# easyeda.net
KiCad netlist of a schematic drawn in EasyEDA
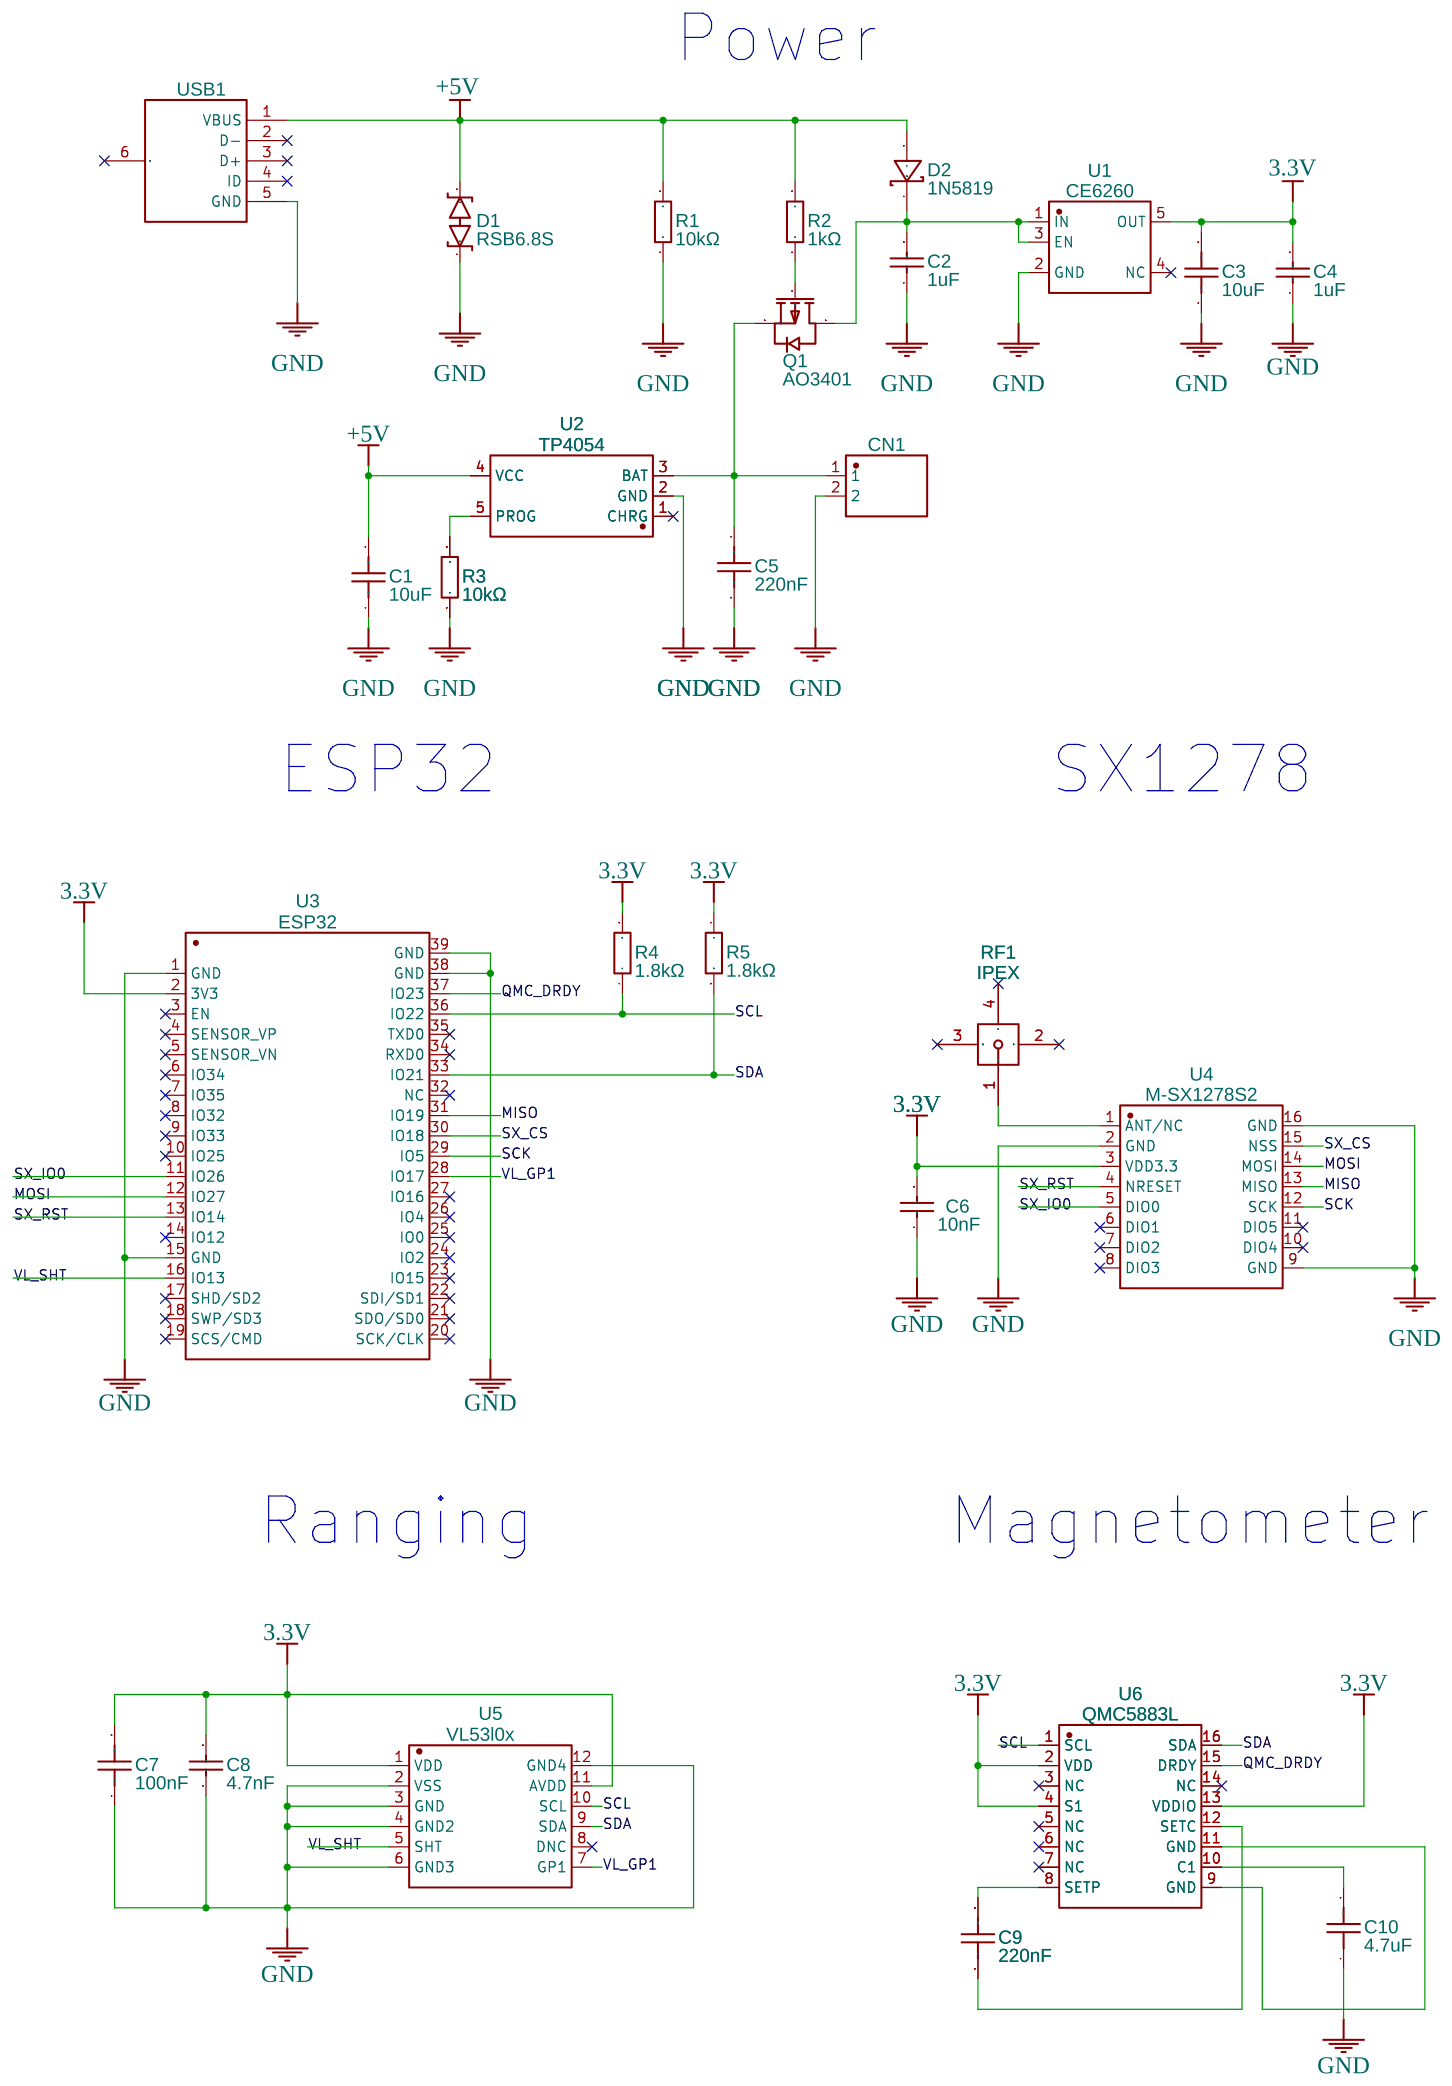
[diagram p0: schematic sheet]

(export (version "E")
  (design (tool "Eeschema 10.0.6"))
  (components
    (comp (ref "C1")
      (value "10uF")
      (fields
        (field (name "Manufacturer Part") "CL10A106KP8NNNC")
        (field (name "Manufacturer") "SAMSUNG(三星)")
      )
      (libsource (lib "") (part "CL10A106KP8NNNC"))
    )
    (comp (ref "C2")
      (value "1uF")
      (fields
        (field (name "Manufacturer Part") "CL05A105KP5NNNC")
        (field (name "Manufacturer") "SAMSUNG(三星)")
      )
      (libsource (lib "") (part "CL05A105KP5NNNC"))
    )
    (comp (ref "C3")
      (value "10uF")
      (fields
        (field (name "Manufacturer Part") "CL10A106KP8NNNC")
        (field (name "Manufacturer") "SAMSUNG(三星)")
      )
      (libsource (lib "") (part "CL10A106KP8NNNC"))
    )
    (comp (ref "C4")
      (value "1uF")
      (fields
        (field (name "Manufacturer Part") "CL05A105KP5NNNC")
        (field (name "Manufacturer") "SAMSUNG(三星)")
      )
      (libsource (lib "") (part "CL05A105KP5NNNC"))
    )
    (comp (ref "C5")
      (value "220nF")
      (fields
        (field (name "Manufacturer Part") "CL05A224KP5NNNC")
        (field (name "Manufacturer") "SAMSUNG(三星)")
      )
      (libsource (lib "") (part "CL05A224KP5NNNC"))
    )
    (comp (ref "C6")
      (value "10nF")
      (fields
        (field (name "Manufacturer Part") "CL10B103KB8NNNC")
        (field (name "Manufacturer") "SAMSUNG(三星)")
      )
      (libsource (lib "") (part "CL10B103KB8NNNC"))
    )
    (comp (ref "C7")
      (value "100nF")
      (fields
        (field (name "Manufacturer Part") "CL10B104KB8NNNC")
        (field (name "Manufacturer") "SAMSUNG(三星)")
      )
      (libsource (lib "") (part "CL10B104KB8NNNC"))
    )
    (comp (ref "C8")
      (value "4.7nF")
      (fields
        (field (name "Manufacturer Part") "CL10B472KB8NNNC")
        (field (name "Manufacturer") "SAMSUNG(三星)")
      )
      (libsource (lib "") (part "CL10B472KB8NNNC"))
    )
    (comp (ref "C9")
      (value "220nF")
      (fields (field (name "Manufacturer Part") "CGA2B1X7R1A224K050BC") (field (name "Manufacturer") "TDK"))
      (libsource (lib "") (part "CGA2B1X7R1A224K050BC"))
    )
    (comp (ref "C10")
      (value "4.7uF")
      (fields
        (field (name "Manufacturer Part") "CL05A475MQ5NRNC")
        (field (name "Manufacturer") "SAMSUNG(三星)")
      )
      (libsource (lib "") (part "CL05A475MQ5NRNC_C307423"))
    )
    (comp (ref "CN1")
      (value "B2B-XH-A (LF)(SN)")
      (fields (field (name "Manufacturer Part") "B2B-XH-A(LF)(SN)") (field (name "Manufacturer") "JST"))
      (libsource (lib "") (part "B2B-XH-A (LF)(SN)"))
    )
    (comp (ref "D1") (value "RSB6.8S") (libsource (lib "") (part "RSB6.8S")))
    (comp (ref "D2")
      (value "1N5819")
      (fields (field (name "Manufacturer") "KEXIN(科信)"))
      (libsource (lib "") (part "1N5819_C437199"))
    )
    (comp (ref "Q1")
      (value "AO3401")
      (fields (field (name "Manufacturer") "YONGYUTAI(永裕泰)"))
      (libsource (lib "") (part "AO3401_C2891730"))
    )
    (comp (ref "R1")
      (value "10kΩ")
      (fields
        (field (name "Manufacturer Part") "0402WGF1002TCE")
        (field (name "Manufacturer") "UNI-ROYAL(厚声)")
      )
      (libsource (lib "") (part "0402WGF1002TCE"))
    )
    (comp (ref "R2")
      (value "1kΩ")
      (fields
        (field (name "Manufacturer Part") "0402WGF1001TCE")
        (field (name "Manufacturer") "UNI-ROYAL(厚声)")
      )
      (libsource (lib "") (part "0402WGF1001TCE"))
    )
    (comp (ref "R3")
      (value "10kΩ")
      (fields
        (field (name "Manufacturer Part") "0402WGF1002TCE")
        (field (name "Manufacturer") "UNI-ROYAL(厚声)")
      )
      (libsource (lib "") (part "0402WGF1002TCE"))
    )
    (comp (ref "R4")
      (value "1.8kΩ")
      (fields
        (field (name "Manufacturer Part") "0402WGF1801TCE")
        (field (name "Manufacturer") "UNI-ROYAL(厚声)")
      )
      (libsource (lib "") (part "0402WGF1801TCE"))
    )
    (comp (ref "R5")
      (value "1.8kΩ")
      (fields
        (field (name "Manufacturer Part") "0402WGF1801TCE")
        (field (name "Manufacturer") "UNI-ROYAL(厚声)")
      )
      (libsource (lib "") (part "0402WGF1801TCE_1"))
    )
    (comp (ref "RF1")
      (value "IPEX")
      (fields (field (name "Manufacturer Part") "IPEX-4") (field (name "Manufacturer") "Ziisor(致哲)"))
      (libsource (lib "") (part "IPEX-4"))
    )
    (comp (ref "U1") (value "CE6260") (libsource (lib "") (part "CE6260_LDO Regulator")))
    (comp (ref "U2")
      (value "TP4054")
      (fields
        (field (name "Manufacturer Part") "TP4054-42-SOT25R")
        (field (name "Manufacturer") "TOPPOWER(南京拓微)")
      )
      (libsource (lib "") (part "TP4054"))
    )
    (comp (ref "U3")
      (value "ESP32")
      (fields
        (field (name "Manufacturer Part") "ESP32-WROOM-32-N4")
        (field (name "Manufacturer") "ESPRESSIF(乐鑫)")
      )
      (libsource (lib "") (part "ESP32-WROOM-32"))
    )
    (comp (ref "U4")
      (value "M-SX1278S2")
      (fields (field (name "Manufacturer") "DreamLNK(骏晔科技)"))
      (libsource (lib "") (part "M-SX1278S2"))
    )
    (comp (ref "U5")
      (value "VL53l0x")
      (fields (field (name "Manufacturer Part") "VL53L0CXV0DH/1") (field (name "Manufacturer") "ST(意法半导体)"))
      (libsource (lib "") (part "VL53L0CXV0DH/1"))
    )
    (comp (ref "U6")
      (value "QMC5883L")
      (fields (field (name "Manufacturer") "QST(上海矽睿)"))
      (libsource (lib "") (part "QMC5883L"))
    )
    (comp (ref "USB1")
      (value "U254-051T-4BH83-S1S")
      (fields (field (name "Manufacturer") "XKB Connectivity(中国星坤)"))
      (libsource (lib "") (part "U254-051T-4BH83-S1S"))
    )
  )
  (nets
    (net (code "1") (name "+5V") (class "Default")
      (node (ref "C1") (pin "2") (pinfunction "2_2") (pintype "unspecified"))
      (node (ref "D1") (pin "2") (pinfunction "2_2") (pintype "unspecified"))
      (node (ref "D2") (pin "2") (pinfunction "A_2") (pintype "unspecified"))
      (node (ref "R1") (pin "2") (pinfunction "2_2") (pintype "input"))
      (node (ref "R2") (pin "2") (pinfunction "2_2") (pintype "input"))
      (node (ref "U2") (pin "4") (pinfunction "VCC_4") (pintype "unspecified"))
      (node (ref "USB1") (pin "1") (pinfunction "VBUS_1") (pintype "input"))
    )
    (net (code "2") (name "/MISO") (class "Default")
      (node (ref "U3") (pin "31") (pinfunction "IO19_31") (pintype "unspecified"))
      (node (ref "U4") (pin "13") (pinfunction "MISO_13") (pintype "unspecified"))
    )
    (net (code "3") (name "/MOSI") (class "Default")
      (node (ref "U3") (pin "12") (pinfunction "IO27_12") (pintype "unspecified"))
      (node (ref "U4") (pin "14") (pinfunction "MOSI_14") (pintype "unspecified"))
    )
    (net (code "4") (name "/QMC_DRDY") (class "Default")
      (node (ref "U3") (pin "37") (pinfunction "IO23_37") (pintype "unspecified"))
      (node (ref "U6") (pin "15") (pinfunction "DRDY_15") (pintype "unspecified"))
    )
    (net (code "5") (name "/SCK") (class "Default")
      (node (ref "U3") (pin "29") (pinfunction "IO5_29") (pintype "unspecified"))
      (node (ref "U4") (pin "12") (pinfunction "SCK_12") (pintype "unspecified"))
    )
    (net (code "6") (name "/SCL") (class "Default")
      (node (ref "R4") (pin "1") (pinfunction "1_1") (pintype "input"))
      (node (ref "U3") (pin "36") (pinfunction "IO22_36") (pintype "unspecified"))
      (node (ref "U5") (pin "10") (pinfunction "SCL_10") (pintype "unspecified"))
      (node (ref "U6") (pin "1") (pinfunction "SCL_1") (pintype "unspecified"))
    )
    (net (code "7") (name "/SDA") (class "Default")
      (node (ref "R5") (pin "2") (pinfunction "2_2") (pintype "input"))
      (node (ref "U3") (pin "33") (pinfunction "IO21_33") (pintype "unspecified"))
      (node (ref "U5") (pin "9") (pinfunction "SDA_9") (pintype "unspecified"))
      (node (ref "U6") (pin "16") (pinfunction "SDA_16") (pintype "unspecified"))
    )
    (net (code "8") (name "/SX_CS") (class "Default")
      (node (ref "U3") (pin "30") (pinfunction "IO18_30") (pintype "unspecified"))
      (node (ref "U4") (pin "15") (pinfunction "NSS_15") (pintype "unspecified"))
    )
    (net (code "9") (name "/SX_IO0") (class "Default")
      (node (ref "U3") (pin "11") (pinfunction "IO26_11") (pintype "unspecified"))
      (node (ref "U4") (pin "5") (pinfunction "DIO0_5") (pintype "unspecified"))
    )
    (net (code "10") (name "/SX_RST") (class "Default")
      (node (ref "U3") (pin "13") (pinfunction "IO14_13") (pintype "unspecified"))
      (node (ref "U4") (pin "4") (pinfunction "NRESET_4") (pintype "unspecified"))
    )
    (net (code "11") (name "/VL_GP1") (class "Default")
      (node (ref "U3") (pin "28") (pinfunction "IO17_28") (pintype "unspecified"))
      (node (ref "U5") (pin "7") (pinfunction "GP1_7") (pintype "unspecified"))
    )
    (net (code "12") (name "/VL_SHT") (class "Default")
      (node (ref "U3") (pin "16") (pinfunction "IO13_16") (pintype "unspecified"))
      (node (ref "U5") (pin "5") (pinfunction "SHT_5") (pintype "unspecified"))
    )
    (net (code "13") (name "3.3V") (class "Default")
      (node (ref "C3") (pin "2") (pinfunction "2_2") (pintype "unspecified"))
      (node (ref "C4") (pin "2") (pinfunction "2_2") (pintype "input"))
      (node (ref "C6") (pin "2") (pinfunction "2_2") (pintype "input"))
      (node (ref "C7") (pin "2") (pinfunction "2_2") (pintype "unspecified"))
      (node (ref "C8") (pin "2") (pinfunction "2_2") (pintype "input"))
      (node (ref "R4") (pin "2") (pinfunction "2_2") (pintype "input"))
      (node (ref "R5") (pin "1") (pinfunction "1_1") (pintype "input"))
      (node (ref "U1") (pin "5") (pinfunction "OUT_5") (pintype "unspecified"))
      (node (ref "U3") (pin "2") (pinfunction "3V3_2") (pintype "unspecified"))
      (node (ref "U4") (pin "3") (pinfunction "VDD3.3_3") (pintype "unspecified"))
      (node (ref "U5") (pin "1") (pinfunction "VDD_1") (pintype "unspecified"))
      (node (ref "U5") (pin "11") (pinfunction "AVDD_11") (pintype "unspecified"))
      (node (ref "U6") (pin "13") (pinfunction "VDDIO_13") (pintype "unspecified"))
      (node (ref "U6") (pin "2") (pinfunction "VDD_2") (pintype "unspecified"))
      (node (ref "U6") (pin "4") (pinfunction "S1_4") (pintype "unspecified"))
    )
    (net (code "14") (name "GND") (class "Default")
      (node (ref "C1") (pin "1") (pinfunction "1_1") (pintype "unspecified"))
      (node (ref "C10") (pin "1") (pinfunction "1_1") (pintype "unspecified"))
      (node (ref "C2") (pin "1") (pinfunction "1_1") (pintype "input"))
      (node (ref "C3") (pin "1") (pinfunction "1_1") (pintype "unspecified"))
      (node (ref "C4") (pin "1") (pinfunction "1_1") (pintype "input"))
      (node (ref "C5") (pin "2") (pinfunction "2_2") (pintype "unspecified"))
      (node (ref "C6") (pin "1") (pinfunction "1_1") (pintype "input"))
      (node (ref "C7") (pin "1") (pinfunction "1_1") (pintype "unspecified"))
      (node (ref "C8") (pin "1") (pinfunction "1_1") (pintype "input"))
      (node (ref "CN1") (pin "2") (pinfunction "2_2") (pintype "unspecified"))
      (node (ref "D1") (pin "1") (pinfunction "1_1") (pintype "unspecified"))
      (node (ref "R1") (pin "1") (pinfunction "1_1") (pintype "input"))
      (node (ref "R3") (pin "1") (pinfunction "1_1") (pintype "input"))
      (node (ref "U1") (pin "2") (pinfunction "GND_2") (pintype "unspecified"))
      (node (ref "U2") (pin "2") (pinfunction "GND_2") (pintype "unspecified"))
      (node (ref "U3") (pin "1") (pinfunction "GND_1") (pintype "unspecified"))
      (node (ref "U3") (pin "15") (pinfunction "GND_15") (pintype "unspecified"))
      (node (ref "U3") (pin "38") (pinfunction "GND_38") (pintype "unspecified"))
      (node (ref "U3") (pin "39") (pinfunction "GND_39") (pintype "unspecified"))
      (node (ref "U4") (pin "16") (pinfunction "GND_16") (pintype "unspecified"))
      (node (ref "U4") (pin "2") (pinfunction "GND_2") (pintype "unspecified"))
      (node (ref "U4") (pin "9") (pinfunction "GND_9") (pintype "unspecified"))
      (node (ref "U5") (pin "12") (pinfunction "GND4_12") (pintype "unspecified"))
      (node (ref "U5") (pin "2") (pinfunction "VSS_2") (pintype "unspecified"))
      (node (ref "U5") (pin "3") (pinfunction "GND_3") (pintype "unspecified"))
      (node (ref "U5") (pin "4") (pinfunction "GND2_4") (pintype "unspecified"))
      (node (ref "U5") (pin "6") (pinfunction "GND3_6") (pintype "unspecified"))
      (node (ref "USB1") (pin "5") (pinfunction "GND_5") (pintype "input"))
    )
    (net (code "15") (name "Net-(D2-C)") (class "Default")
      (node (ref "C2") (pin "2") (pinfunction "2_2") (pintype "input"))
      (node (ref "D2") (pin "1") (pinfunction "C_1") (pintype "unspecified"))
      (node (ref "Q1") (pin "3") (pinfunction "D_3") (pintype "unspecified"))
      (node (ref "U1") (pin "1") (pinfunction "IN_1") (pintype "unspecified"))
      (node (ref "U1") (pin "3") (pinfunction "EN_3") (pintype "unspecified"))
    )
    (net (code "16") (name "Net-(Q1-G)") (class "Default")
      (node (ref "Q1") (pin "1") (pinfunction "G_1") (pintype "unspecified"))
      (node (ref "R2") (pin "1") (pinfunction "1_1") (pintype "input"))
    )
    (net (code "17") (name "Net-(Q1-S)") (class "Default")
      (node (ref "C5") (pin "1") (pinfunction "1_1") (pintype "unspecified"))
      (node (ref "CN1") (pin "1") (pinfunction "1_1") (pintype "unspecified"))
      (node (ref "Q1") (pin "2") (pinfunction "S_2") (pintype "unspecified"))
      (node (ref "U2") (pin "3") (pinfunction "BAT_3") (pintype "unspecified"))
    )
    (net (code "18") (name "Net-(U2-PROG)") (class "Default")
      (node (ref "R3") (pin "2") (pinfunction "2_2") (pintype "input"))
      (node (ref "U2") (pin "5") (pinfunction "PROG_5") (pintype "unspecified"))
    )
    (net (code "19") (name "Net-(U4-ANT{slash}NC)") (class "Default")
      (node (ref "RF1") (pin "1") (pinfunction "1_1") (pintype "unspecified"))
      (node (ref "U4") (pin "1") (pinfunction "ANT/NC_1") (pintype "unspecified"))
    )
    (net (code "20") (name "Net-(U6-C1)") (class "Default")
      (node (ref "C10") (pin "2") (pinfunction "2_2") (pintype "unspecified"))
      (node (ref "U6") (pin "10") (pinfunction "C1_10") (pintype "unspecified"))
    )
    (net (code "21") (name "Net-(U6-GND-Pad11)") (class "Default")
      (node (ref "U6") (pin "11") (pinfunction "GND_11") (pintype "unspecified"))
      (node (ref "U6") (pin "9") (pinfunction "GND_9") (pintype "unspecified"))
    )
    (net (code "22") (name "Net-(U6-SETC)") (class "Default")
      (node (ref "C9") (pin "1") (pinfunction "1_1") (pintype "unspecified"))
      (node (ref "U6") (pin "12") (pinfunction "SETC_12") (pintype "unspecified"))
    )
    (net (code "23") (name "Net-(U6-SETP)") (class "Default")
      (node (ref "C9") (pin "2") (pinfunction "2_2") (pintype "unspecified"))
      (node (ref "U6") (pin "8") (pinfunction "SETP_8") (pintype "unspecified"))
    )
    (net (code "24") (name "unconnected-(RF1-Pad2)") (class "Default")
      (node (ref "RF1") (pin "2") (pinfunction "2_2") (pintype "unspecified+no_connect"))
    )
    (net (code "25") (name "unconnected-(RF1-Pad3)") (class "Default")
      (node (ref "RF1") (pin "3") (pinfunction "3_3") (pintype "unspecified+no_connect"))
    )
    (net (code "26") (name "unconnected-(RF1-Pad4)") (class "Default")
      (node (ref "RF1") (pin "4") (pinfunction "4_4") (pintype "unspecified+no_connect"))
    )
    (net (code "27") (name "unconnected-(U1-NC-Pad4)") (class "Default")
      (node (ref "U1") (pin "4") (pinfunction "NC_4") (pintype "unspecified+no_connect"))
    )
    (net (code "28") (name "unconnected-(U2-CHRG-Pad1)") (class "Default")
      (node (ref "U2") (pin "1") (pinfunction "CHRG_1") (pintype "unspecified+no_connect"))
    )
    (net (code "29") (name "unconnected-(U3-EN-Pad3)") (class "Default")
      (node (ref "U3") (pin "3") (pinfunction "EN_3") (pintype "unspecified+no_connect"))
    )
    (net (code "30") (name "unconnected-(U3-IO0-Pad25)") (class "Default")
      (node (ref "U3") (pin "25") (pinfunction "IO0_25") (pintype "unspecified+no_connect"))
    )
    (net (code "31") (name "unconnected-(U3-IO2-Pad24)") (class "Default")
      (node (ref "U3") (pin "24") (pinfunction "IO2_24") (pintype "unspecified+no_connect"))
    )
    (net (code "32") (name "unconnected-(U3-IO4-Pad26)") (class "Default")
      (node (ref "U3") (pin "26") (pinfunction "IO4_26") (pintype "unspecified+no_connect"))
    )
    (net (code "33") (name "unconnected-(U3-IO12-Pad14)") (class "Default")
      (node (ref "U3") (pin "14") (pinfunction "IO12_14") (pintype "unspecified+no_connect"))
    )
    (net (code "34") (name "unconnected-(U3-IO15-Pad23)") (class "Default")
      (node (ref "U3") (pin "23") (pinfunction "IO15_23") (pintype "unspecified+no_connect"))
    )
    (net (code "35") (name "unconnected-(U3-IO16-Pad27)") (class "Default")
      (node (ref "U3") (pin "27") (pinfunction "IO16_27") (pintype "unspecified+no_connect"))
    )
    (net (code "36") (name "unconnected-(U3-IO25-Pad10)") (class "Default")
      (node (ref "U3") (pin "10") (pinfunction "IO25_10") (pintype "unspecified+no_connect"))
    )
    (net (code "37") (name "unconnected-(U3-IO32-Pad8)") (class "Default")
      (node (ref "U3") (pin "8") (pinfunction "IO32_8") (pintype "unspecified+no_connect"))
    )
    (net (code "38") (name "unconnected-(U3-IO33-Pad9)") (class "Default")
      (node (ref "U3") (pin "9") (pinfunction "IO33_9") (pintype "unspecified+no_connect"))
    )
    (net (code "39") (name "unconnected-(U3-IO34-Pad6)") (class "Default")
      (node (ref "U3") (pin "6") (pinfunction "IO34_6") (pintype "unspecified+no_connect"))
    )
    (net (code "40") (name "unconnected-(U3-IO35-Pad7)") (class "Default")
      (node (ref "U3") (pin "7") (pinfunction "IO35_7") (pintype "unspecified+no_connect"))
    )
    (net (code "41") (name "unconnected-(U3-NC-Pad32)") (class "Default")
      (node (ref "U3") (pin "32") (pinfunction "NC_32") (pintype "unspecified+no_connect"))
    )
    (net (code "42") (name "unconnected-(U3-RXD0-Pad34)") (class "Default")
      (node (ref "U3") (pin "34") (pinfunction "RXD0_34") (pintype "unspecified+no_connect"))
    )
    (net (code "43") (name "unconnected-(U3-SCK{slash}CLK-Pad20)") (class "Default")
      (node (ref "U3") (pin "20") (pinfunction "SCK/CLK_20") (pintype "unspecified+no_connect"))
    )
    (net (code "44") (name "unconnected-(U3-SCS{slash}CMD-Pad19)") (class "Default")
      (node (ref "U3") (pin "19") (pinfunction "SCS/CMD_19") (pintype "unspecified+no_connect"))
    )
    (net (code "45") (name "unconnected-(U3-SDI{slash}SD1-Pad22)") (class "Default")
      (node (ref "U3") (pin "22") (pinfunction "SDI/SD1_22") (pintype "unspecified+no_connect"))
    )
    (net (code "46") (name "unconnected-(U3-SDO{slash}SD0-Pad21)") (class "Default")
      (node (ref "U3") (pin "21") (pinfunction "SDO/SD0_21") (pintype "unspecified+no_connect"))
    )
    (net (code "47") (name "unconnected-(U3-SENSOR_VN-Pad5)") (class "Default")
      (node (ref "U3") (pin "5") (pinfunction "SENSOR_VN_5") (pintype "unspecified+no_connect"))
    )
    (net (code "48") (name "unconnected-(U3-SENSOR_VP-Pad4)") (class "Default")
      (node (ref "U3") (pin "4") (pinfunction "SENSOR_VP_4") (pintype "unspecified+no_connect"))
    )
    (net (code "49") (name "unconnected-(U3-SHD{slash}SD2-Pad17)") (class "Default")
      (node (ref "U3") (pin "17") (pinfunction "SHD/SD2_17") (pintype "unspecified+no_connect"))
    )
    (net (code "50") (name "unconnected-(U3-SWP{slash}SD3-Pad18)") (class "Default")
      (node (ref "U3") (pin "18") (pinfunction "SWP/SD3_18") (pintype "unspecified+no_connect"))
    )
    (net (code "51") (name "unconnected-(U3-TXD0-Pad35)") (class "Default")
      (node (ref "U3") (pin "35") (pinfunction "TXD0_35") (pintype "unspecified+no_connect"))
    )
    (net (code "52") (name "unconnected-(U4-DIO1-Pad6)") (class "Default")
      (node (ref "U4") (pin "6") (pinfunction "DIO1_6") (pintype "unspecified+no_connect"))
    )
    (net (code "53") (name "unconnected-(U4-DIO2-Pad7)") (class "Default")
      (node (ref "U4") (pin "7") (pinfunction "DIO2_7") (pintype "unspecified+no_connect"))
    )
    (net (code "54") (name "unconnected-(U4-DIO3-Pad8)") (class "Default")
      (node (ref "U4") (pin "8") (pinfunction "DIO3_8") (pintype "unspecified+no_connect"))
    )
    (net (code "55") (name "unconnected-(U4-DIO4-Pad10)") (class "Default")
      (node (ref "U4") (pin "10") (pinfunction "DIO4_10") (pintype "unspecified+no_connect"))
    )
    (net (code "56") (name "unconnected-(U4-DIO5-Pad11)") (class "Default")
      (node (ref "U4") (pin "11") (pinfunction "DIO5_11") (pintype "unspecified+no_connect"))
    )
    (net (code "57") (name "unconnected-(U5-DNC-Pad8)") (class "Default")
      (node (ref "U5") (pin "8") (pinfunction "DNC_8") (pintype "unspecified+no_connect"))
    )
    (net (code "58") (name "unconnected-(U6-NC-Pad3)") (class "Default")
      (node (ref "U6") (pin "3") (pinfunction "NC_3") (pintype "unspecified+no_connect"))
    )
    (net (code "59") (name "unconnected-(U6-NC-Pad5)") (class "Default")
      (node (ref "U6") (pin "5") (pinfunction "NC_5") (pintype "unspecified+no_connect"))
    )
    (net (code "60") (name "unconnected-(U6-NC-Pad6)") (class "Default")
      (node (ref "U6") (pin "6") (pinfunction "NC_6") (pintype "unspecified+no_connect"))
    )
    (net (code "61") (name "unconnected-(U6-NC-Pad7)") (class "Default")
      (node (ref "U6") (pin "7") (pinfunction "NC_7") (pintype "unspecified+no_connect"))
    )
    (net (code "62") (name "unconnected-(U6-NC-Pad14)") (class "Default")
      (node (ref "U6") (pin "14") (pinfunction "NC_14") (pintype "unspecified+no_connect"))
    )
    (net (code "63") (name "unconnected-(USB1-D+-Pad3)") (class "Default")
      (node (ref "USB1") (pin "3") (pinfunction "D+_3") (pintype "input+no_connect"))
    )
    (net (code "64") (name "unconnected-(USB1-D--Pad2)") (class "Default")
      (node (ref "USB1") (pin "2") (pinfunction "D-_2") (pintype "input+no_connect"))
    )
    (net (code "65") (name "unconnected-(USB1-EH-Pad6)") (class "Default")
      (node (ref "USB1") (pin "6") (pinfunction "EH_6") (pintype "input+no_connect"))
    )
    (net (code "66") (name "unconnected-(USB1-ID-Pad4)") (class "Default")
      (node (ref "USB1") (pin "4") (pinfunction "ID_4") (pintype "input+no_connect"))
    )
  )
)
